# LAUNCHXL-F28377S_2.net
KiCad netlist of a schematic drawn in Altium Designer
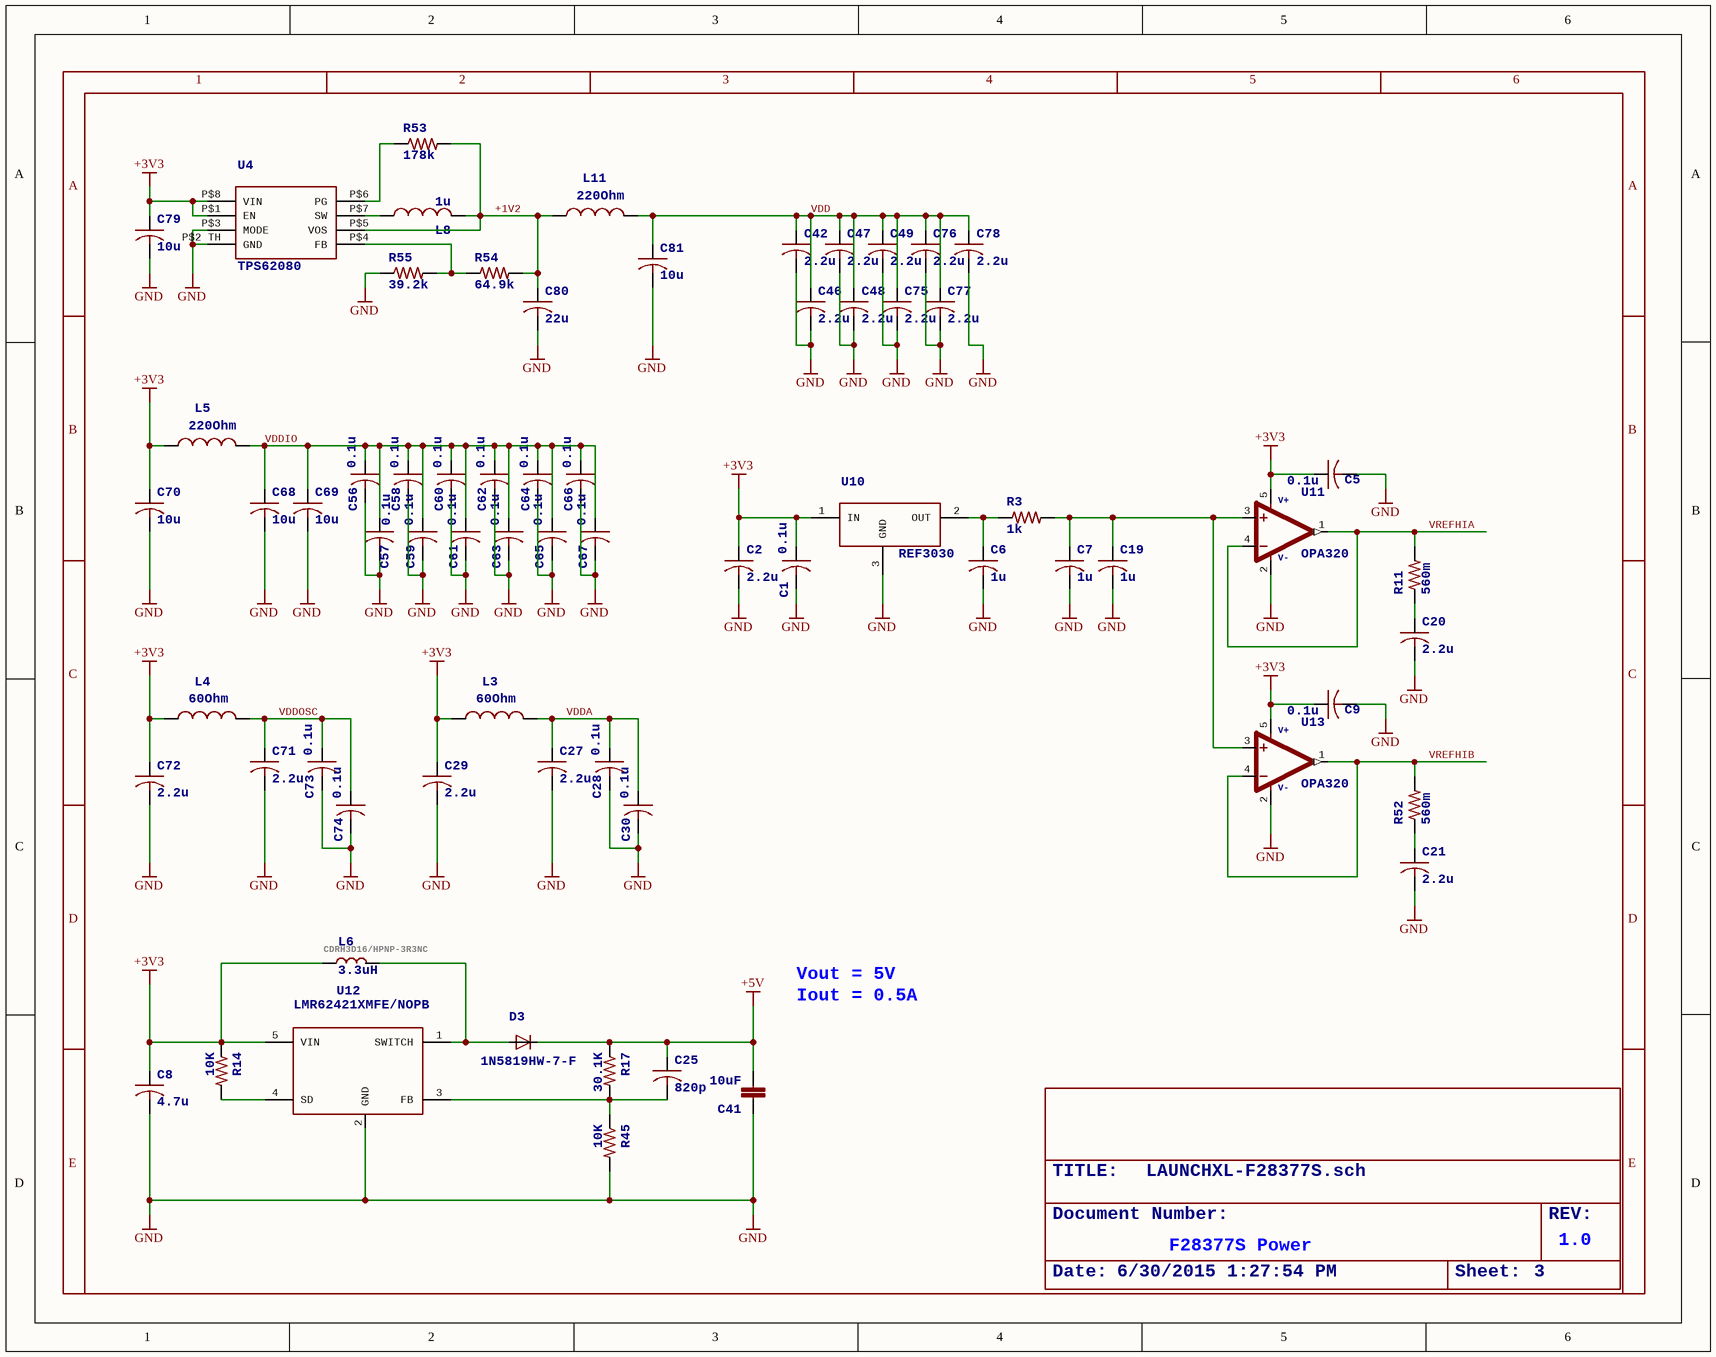
[diagram p0: LAUNCHXL-F28377S_2.SchDoc]

(export (version "E")
  (design (tool "Eeschema 10.0.6"))
  (components
    (comp (ref "C1")
      (value "0.1u")
      (footprint "C0402")
      (description "<B>CAPACITOR</B>, American symbol")
      (libsource (lib "rcl") (part "C-USC0402"))
    )
    (comp (ref "C2")
      (value "2.2u")
      (footprint "C0402")
      (description "<B>CAPACITOR</B>, American symbol")
      (libsource (lib "rcl") (part "C-USC0402"))
    )
    (comp (ref "C5")
      (value "0.1u")
      (footprint "C0402")
      (description "<B>CAPACITOR</B>, American symbol")
      (libsource (lib "rcl") (part "C-USC0402"))
    )
    (comp (ref "C6")
      (value "1u")
      (footprint "C0402")
      (description "<B>CAPACITOR</B>, American symbol")
      (libsource (lib "rcl") (part "C-USC0402"))
    )
    (comp (ref "C7")
      (value "1u")
      (footprint "C0402")
      (description "<B>CAPACITOR</B>, American symbol")
      (libsource (lib "rcl") (part "C-USC0402"))
    )
    (comp (ref "C8")
      (value "4.7u")
      (footprint "C0402")
      (description "<B>CAPACITOR</B>, American symbol")
      (libsource (lib "rcl") (part "C-USC0402"))
    )
    (comp (ref "C9")
      (value "0.1u")
      (footprint "C0402")
      (description "<B>CAPACITOR</B>, American symbol")
      (libsource (lib "rcl") (part "C-USC0402"))
    )
    (comp (ref "C19")
      (value "1u")
      (footprint "C0402")
      (description "<B>CAPACITOR</B>, American symbol")
      (libsource (lib "rcl") (part "C-USC0402"))
    )
    (comp (ref "C20")
      (value "2.2u")
      (footprint "C0402")
      (description "<B>CAPACITOR</B>, American symbol")
      (libsource (lib "rcl") (part "C-USC0402"))
    )
    (comp (ref "C21")
      (value "2.2u")
      (footprint "C0402")
      (description "<B>CAPACITOR</B>, American symbol")
      (libsource (lib "rcl") (part "C-USC0402"))
    )
    (comp (ref "C25")
      (value "820p")
      (footprint "C0402")
      (description "<B>CAPACITOR</B>, American symbol")
      (libsource (lib "rcl") (part "C-USC0402"))
    )
    (comp (ref "C27")
      (value "2.2u")
      (footprint "C0402")
      (description "<B>CAPACITOR</B>, American symbol")
      (libsource (lib "rcl") (part "C-USC0402"))
    )
    (comp (ref "C28")
      (value "0.1u")
      (footprint "C0402")
      (description "<B>CAPACITOR</B>, American symbol")
      (libsource (lib "rcl") (part "C-USC0402"))
    )
    (comp (ref "C29")
      (value "2.2u")
      (footprint "C0402")
      (description "<B>CAPACITOR</B>, American symbol")
      (libsource (lib "rcl") (part "C-USC0402"))
    )
    (comp (ref "C30")
      (value "0.1u")
      (footprint "C0402")
      (description "<B>CAPACITOR</B>, American symbol")
      (libsource (lib "rcl") (part "C-USC0402"))
    )
    (comp (ref "C41")
      (value "10uF")
      (footprint "SPARKFUN_1210")
      (description "<b>Capacitor</b>\nStandard 0603 ceramic capacitor, and 0.1\" leaded capacitor.")
      (libsource (lib "RF430FRL152H_EVM_a") (part "SPARKFUN_CAP1210"))
    )
    (comp (ref "C42")
      (value "2.2u")
      (footprint "C0402")
      (description "<B>CAPACITOR</B>, American symbol")
      (libsource (lib "rcl") (part "C-USC0402"))
    )
    (comp (ref "C46")
      (value "2.2u")
      (footprint "C0402")
      (description "<B>CAPACITOR</B>, American symbol")
      (libsource (lib "rcl") (part "C-USC0402"))
    )
    (comp (ref "C47")
      (value "2.2u")
      (footprint "C0402")
      (description "<B>CAPACITOR</B>, American symbol")
      (libsource (lib "rcl") (part "C-USC0402"))
    )
    (comp (ref "C48")
      (value "2.2u")
      (footprint "C0402")
      (description "<B>CAPACITOR</B>, American symbol")
      (libsource (lib "rcl") (part "C-USC0402"))
    )
    (comp (ref "C49")
      (value "2.2u")
      (footprint "C0402")
      (description "<B>CAPACITOR</B>, American symbol")
      (libsource (lib "rcl") (part "C-USC0402"))
    )
    (comp (ref "C56")
      (value "0.1u")
      (footprint "C0402")
      (description "<B>CAPACITOR</B>, American symbol")
      (libsource (lib "rcl") (part "C-USC0402"))
    )
    (comp (ref "C57")
      (value "0.1u")
      (footprint "C0402")
      (description "<B>CAPACITOR</B>, American symbol")
      (libsource (lib "") (part "C-USC0402_1"))
    )
    (comp (ref "C58")
      (value "0.1u")
      (footprint "C0402")
      (description "<B>CAPACITOR</B>, American symbol")
      (libsource (lib "rcl") (part "C-USC0402"))
    )
    (comp (ref "C59")
      (value "0.1u")
      (footprint "C0402")
      (description "<B>CAPACITOR</B>, American symbol")
      (libsource (lib "rcl") (part "C-USC0402"))
    )
    (comp (ref "C60")
      (value "0.1u")
      (footprint "C0402")
      (description "<B>CAPACITOR</B>, American symbol")
      (libsource (lib "rcl") (part "C-USC0402"))
    )
    (comp (ref "C61")
      (value "0.1u")
      (footprint "C0402")
      (description "<B>CAPACITOR</B>, American symbol")
      (libsource (lib "rcl") (part "C-USC0402"))
    )
    (comp (ref "C62")
      (value "0.1u")
      (footprint "C0402")
      (description "<B>CAPACITOR</B>, American symbol")
      (libsource (lib "rcl") (part "C-USC0402"))
    )
    (comp (ref "C63")
      (value "0.1u")
      (footprint "C0402")
      (description "<B>CAPACITOR</B>, American symbol")
      (libsource (lib "rcl") (part "C-USC0402"))
    )
    (comp (ref "C64")
      (value "0.1u")
      (footprint "C0402")
      (description "<B>CAPACITOR</B>, American symbol")
      (libsource (lib "rcl") (part "C-USC0402"))
    )
    (comp (ref "C65")
      (value "0.1u")
      (footprint "C0402")
      (description "<B>CAPACITOR</B>, American symbol")
      (libsource (lib "rcl") (part "C-USC0402"))
    )
    (comp (ref "C66")
      (value "0.1u")
      (footprint "C0402")
      (description "<B>CAPACITOR</B>, American symbol")
      (libsource (lib "rcl") (part "C-USC0402"))
    )
    (comp (ref "C67")
      (value "0.1u")
      (footprint "C0402")
      (description "<B>CAPACITOR</B>, American symbol")
      (libsource (lib "rcl") (part "C-USC0402"))
    )
    (comp (ref "C68")
      (value "10u")
      (footprint "C0603")
      (description "<B>CAPACITOR</B>, American symbol")
      (libsource (lib "rcl") (part "C-USC0603"))
    )
    (comp (ref "C69")
      (value "10u")
      (footprint "C0603")
      (description "<B>CAPACITOR</B>, American symbol")
      (libsource (lib "rcl") (part "C-USC0603"))
    )
    (comp (ref "C70")
      (value "10u")
      (footprint "C0603")
      (description "<B>CAPACITOR</B>, American symbol")
      (libsource (lib "rcl") (part "C-USC0603"))
    )
    (comp (ref "C71")
      (value "2.2u")
      (footprint "C0402")
      (description "<B>CAPACITOR</B>, American symbol")
      (libsource (lib "rcl") (part "C-USC0402"))
    )
    (comp (ref "C72")
      (value "2.2u")
      (footprint "C0402")
      (description "<B>CAPACITOR</B>, American symbol")
      (libsource (lib "rcl") (part "C-USC0402"))
    )
    (comp (ref "C73")
      (value "0.1u")
      (footprint "C0402")
      (description "<B>CAPACITOR</B>, American symbol")
      (libsource (lib "rcl") (part "C-USC0402"))
    )
    (comp (ref "C74")
      (value "0.1u")
      (footprint "C0402")
      (description "<B>CAPACITOR</B>, American symbol")
      (libsource (lib "rcl") (part "C-USC0402"))
    )
    (comp (ref "C75")
      (value "2.2u")
      (footprint "C0402")
      (description "<B>CAPACITOR</B>, American symbol")
      (libsource (lib "rcl") (part "C-USC0402"))
    )
    (comp (ref "C76")
      (value "2.2u")
      (footprint "C0402")
      (description "<B>CAPACITOR</B>, American symbol")
      (libsource (lib "rcl") (part "C-USC0402"))
    )
    (comp (ref "C77")
      (value "2.2u")
      (footprint "C0402")
      (description "<B>CAPACITOR</B>, American symbol")
      (libsource (lib "rcl") (part "C-USC0402"))
    )
    (comp (ref "C78")
      (value "2.2u")
      (footprint "C0402")
      (description "<B>CAPACITOR</B>, American symbol")
      (libsource (lib "rcl") (part "C-USC0402"))
    )
    (comp (ref "C79")
      (value "10u")
      (footprint "C0603")
      (description "<B>CAPACITOR</B>, American symbol")
      (libsource (lib "rcl") (part "C-USC0603"))
    )
    (comp (ref "C80")
      (value "22u")
      (footprint "C0603")
      (description "<B>CAPACITOR</B>, American symbol")
      (libsource (lib "rcl") (part "C-USC0603"))
    )
    (comp (ref "C81")
      (value "10u")
      (footprint "C0603")
      (description "<B>CAPACITOR</B>, American symbol")
      (libsource (lib "rcl") (part "C-USC0603"))
    )
    (comp (ref "D3")
      (value "1N5819HW-7-F")
      (footprint "SOD123")
      (description "<B>DIODE</B><p>\nhigh speed (Philips)")
      (libsource (lib "diode") (part "1N4148"))
    )
    (comp (ref "FRAME8")
      (value "FRAME_A_L")
      (description "<b>FRAME</b> A Size , 8 1/2 x 11 INCH, Landscape<p>")
      (fields
        (field (name "DATE:") "Date:")
        (field (name ">LAST_DATE_TIME") "6/30/2015 1:27:54 PM")
        (field (name "SHEET:") "Sheet:")
        (field (name ">SHEET") "3")
        (field (name "REV:") "REV:")
        (field (name "TITLE:") "TITLE:")
        (field (name "DOCUMENT NUMBER:") "Document Number:")
        (field (name ">DRAWING_NAME") "LAUNCHXL-F28377S.sch")
      )
      (libsource (lib "frames") (part "FRAME_A_L"))
    )
    (comp (ref "L3")
      (value "60Ohm")
      (footprint "R0402")
      (description "<B>INDUCTOR</B>, American symbol")
      (libsource (lib "rcl") (part "L-US0402"))
    )
    (comp (ref "L4")
      (value "60Ohm")
      (footprint "R0402")
      (description "<B>INDUCTOR</B>, American symbol")
      (libsource (lib "rcl") (part "L-US0402"))
    )
    (comp (ref "L5")
      (value "220Ohm")
      (footprint "R0402")
      (description "<B>INDUCTOR</B>, American symbol")
      (libsource (lib "rcl") (part "L-US0402"))
    )
    (comp (ref "L6")
      (value "3.3uH")
      (footprint "INDUCT-3_7*3_5")
      (libsource (lib "LAUNCHXL-F28027") (part "VLF4012A"))
    )
    (comp (ref "L8")
      (value "1u")
      (footprint "L1212")
      (description "<B>INDUCTOR</B>, American symbol")
      (libsource (lib "LAUNCHXL-F28377S") (part "L-USL1212"))
    )
    (comp (ref "L11")
      (value "220Ohm")
      (footprint "R0402")
      (description "<B>INDUCTOR</B>, American symbol")
      (libsource (lib "rcl") (part "L-US0402"))
    )
    (comp (ref "R3")
      (value "1k")
      (footprint "R0402")
      (description "<B>RESISTOR</B>, American symbol")
      (libsource (lib "rcl") (part "R-US_R0402"))
    )
    (comp (ref "R11")
      (value "560m")
      (footprint "R0402")
      (description "<B>RESISTOR</B>, American symbol")
      (libsource (lib "rcl") (part "R-US_R0402"))
    )
    (comp (ref "R14")
      (value "10K")
      (footprint "R0402")
      (description "<B>RESISTOR</B>, American symbol")
      (libsource (lib "rcl") (part "R-US_R0402"))
    )
    (comp (ref "R17")
      (value "30.1K")
      (footprint "R0402")
      (description "<B>RESISTOR</B>, American symbol")
      (libsource (lib "rcl") (part "R-US_R0402"))
    )
    (comp (ref "R45")
      (value "10K")
      (footprint "R0402")
      (description "<B>RESISTOR</B>, American symbol")
      (libsource (lib "rcl") (part "R-US_R0402"))
    )
    (comp (ref "R52")
      (value "560m")
      (footprint "R0402")
      (description "<B>RESISTOR</B>, American symbol")
      (libsource (lib "rcl") (part "R-US_R0402"))
    )
    (comp (ref "R53")
      (value "178k")
      (footprint "R0402")
      (description "<B>RESISTOR</B>, American symbol")
      (libsource (lib "rcl") (part "R-US_R0402"))
    )
    (comp (ref "R54")
      (value "64.9k")
      (footprint "R0402")
      (description "<B>RESISTOR</B>, American symbol")
      (libsource (lib "rcl") (part "R-US_R0402"))
    )
    (comp (ref "R55")
      (value "39.2k")
      (footprint "R0402")
      (description "<B>RESISTOR</B>, American symbol")
      (libsource (lib "rcl") (part "R-US_R0402"))
    )
    (comp (ref "U4")
      (value "TPS62080")
      (footprint "SON8")
      (libsource (lib "LAUNCHXL-F28377S") (part "TPS62080"))
    )
    (comp (ref "U10")
      (value "REF3030")
      (footprint "DBZ_R-PDSO-G3")
      (libsource (lib "LAUNCHXL-F28377S") (part "REF30XX"))
    )
    (comp (ref "U11")
      (value "OPA320")
      (footprint "SOT23-5-DBV")
      (fields (field (name "V+") "V+") (field (name "V-") "V-"))
      (libsource (lib "LAUNCHXL-F28377S") (part "OPA320"))
    )
    (comp (ref "U12")
      (value "LMR62421XMFE/NOPB")
      (footprint "SOT23-5-DBV")
      (libsource (lib "LAUNCHXL-F28027") (part "LMR62421XMFE/NOPB"))
    )
    (comp (ref "U13")
      (value "OPA320")
      (footprint "SOT23-5-DBV")
      (fields (field (name "V+") "V+") (field (name "V-") "V-"))
      (libsource (lib "LAUNCHXL-F28377S") (part "OPA320"))
    )
  )
  (nets
    (net (code "1") (name "+3V3") (class "Default")
      (node (ref "C1") (pin "1") (pinfunction "1_1") (pintype "passive"))
      (node (ref "C2") (pin "1") (pinfunction "1_1") (pintype "passive"))
      (node (ref "C29") (pin "1") (pinfunction "1_1") (pintype "passive"))
      (node (ref "C5") (pin "1") (pinfunction "1_1") (pintype "passive"))
      (node (ref "C70") (pin "1") (pinfunction "1_1") (pintype "passive"))
      (node (ref "C72") (pin "1") (pinfunction "1_1") (pintype "passive"))
      (node (ref "C79") (pin "1") (pinfunction "1_1") (pintype "passive"))
      (node (ref "C8") (pin "1") (pinfunction "1_1") (pintype "passive"))
      (node (ref "C9") (pin "1") (pinfunction "1_1") (pintype "passive"))
      (node (ref "L3") (pin "1") (pinfunction "1_1") (pintype "passive"))
      (node (ref "L4") (pin "1") (pinfunction "1_1") (pintype "passive"))
      (node (ref "L5") (pin "1") (pinfunction "1_1") (pintype "passive"))
      (node (ref "L6") (pin "P$1") (pinfunction "1_P$1") (pintype "passive"))
      (node (ref "R14") (pin "1") (pinfunction "1_1") (pintype "passive"))
      (node (ref "U10") (pin "1") (pinfunction "IN_1") (pintype "passive"))
      (node (ref "U11") (pin "5") (pinfunction "V+_5") (pintype "power_in"))
      (node (ref "U12") (pin "5") (pinfunction "VIN_5") (pintype "passive"))
      (node (ref "U13") (pin "5") (pinfunction "V+_5") (pintype "power_in"))
      (node (ref "U4") (pin "P$1") (pinfunction "EN_P$1") (pintype "passive"))
      (node (ref "U4") (pin "P$8") (pinfunction "VIN_P$8") (pintype "passive"))
    )
    (net (code "2") (name "+5V") (class "Default")
      (node (ref "C25") (pin "1") (pinfunction "1_1") (pintype "passive"))
      (node (ref "C41") (pin "2") (pinfunction "2_2") (pintype "passive"))
      (node (ref "D3") (pin "C") (pinfunction "C_C") (pintype "passive"))
      (node (ref "R17") (pin "1") (pinfunction "1_1") (pintype "passive"))
    )
    (net (code "3") (name "/+1V2") (class "Default")
      (node (ref "C80") (pin "1") (pinfunction "1_1") (pintype "passive"))
      (node (ref "L11") (pin "1") (pinfunction "1_1") (pintype "passive"))
      (node (ref "L8") (pin "P$2") (pinfunction "2_P$2") (pintype "passive"))
      (node (ref "R53") (pin "2") (pinfunction "2_2") (pintype "passive"))
      (node (ref "R54") (pin "2") (pinfunction "2_2") (pintype "passive"))
      (node (ref "U4") (pin "P$5") (pinfunction "VOS_P$5") (pintype "passive"))
    )
    (net (code "4") (name "/VDD") (class "Default")
      (node (ref "C42") (pin "1") (pinfunction "1_1") (pintype "passive"))
      (node (ref "C46") (pin "1") (pinfunction "1_1") (pintype "passive"))
      (node (ref "C47") (pin "1") (pinfunction "1_1") (pintype "passive"))
      (node (ref "C48") (pin "1") (pinfunction "1_1") (pintype "passive"))
      (node (ref "C49") (pin "1") (pinfunction "1_1") (pintype "passive"))
      (node (ref "C75") (pin "1") (pinfunction "1_1") (pintype "passive"))
      (node (ref "C76") (pin "1") (pinfunction "1_1") (pintype "passive"))
      (node (ref "C77") (pin "1") (pinfunction "1_1") (pintype "passive"))
      (node (ref "C78") (pin "1") (pinfunction "1_1") (pintype "passive"))
      (node (ref "C81") (pin "1") (pinfunction "1_1") (pintype "passive"))
      (node (ref "L11") (pin "2") (pinfunction "2_2") (pintype "passive"))
    )
    (net (code "5") (name "/VDDA") (class "Default")
      (node (ref "C27") (pin "1") (pinfunction "1_1") (pintype "passive"))
      (node (ref "C28") (pin "1") (pinfunction "1_1") (pintype "passive"))
      (node (ref "C30") (pin "1") (pinfunction "1_1") (pintype "passive"))
      (node (ref "L3") (pin "2") (pinfunction "2_2") (pintype "passive"))
    )
    (net (code "6") (name "/VDDIO") (class "Default")
      (node (ref "C56") (pin "1") (pinfunction "1_1") (pintype "passive"))
      (node (ref "C57") (pin "1") (pinfunction "1_1") (pintype "passive"))
      (node (ref "C58") (pin "1") (pinfunction "1_1") (pintype "passive"))
      (node (ref "C59") (pin "1") (pinfunction "1_1") (pintype "passive"))
      (node (ref "C60") (pin "1") (pinfunction "1_1") (pintype "passive"))
      (node (ref "C61") (pin "1") (pinfunction "1_1") (pintype "passive"))
      (node (ref "C62") (pin "1") (pinfunction "1_1") (pintype "passive"))
      (node (ref "C63") (pin "1") (pinfunction "1_1") (pintype "passive"))
      (node (ref "C64") (pin "1") (pinfunction "1_1") (pintype "passive"))
      (node (ref "C65") (pin "1") (pinfunction "1_1") (pintype "passive"))
      (node (ref "C66") (pin "1") (pinfunction "1_1") (pintype "passive"))
      (node (ref "C67") (pin "1") (pinfunction "1_1") (pintype "passive"))
      (node (ref "C68") (pin "1") (pinfunction "1_1") (pintype "passive"))
      (node (ref "C69") (pin "1") (pinfunction "1_1") (pintype "passive"))
      (node (ref "L5") (pin "2") (pinfunction "2_2") (pintype "passive"))
    )
    (net (code "7") (name "/VDDOSC") (class "Default")
      (node (ref "C71") (pin "1") (pinfunction "1_1") (pintype "passive"))
      (node (ref "C73") (pin "1") (pinfunction "1_1") (pintype "passive"))
      (node (ref "C74") (pin "1") (pinfunction "1_1") (pintype "passive"))
      (node (ref "L4") (pin "2") (pinfunction "2_2") (pintype "passive"))
    )
    (net (code "8") (name "/VREFHIA") (class "Default")
      (node (ref "R11") (pin "2") (pinfunction "2_2") (pintype "passive"))
      (node (ref "U11") (pin "1") (pinfunction "OUT_1") (pintype "output"))
      (node (ref "U11") (pin "4") (pinfunction "-IN_4") (pintype "passive"))
    )
    (net (code "9") (name "/VREFHIB") (class "Default")
      (node (ref "R52") (pin "2") (pinfunction "2_2") (pintype "passive"))
      (node (ref "U13") (pin "1") (pinfunction "OUT_1") (pintype "output"))
      (node (ref "U13") (pin "4") (pinfunction "-IN_4") (pintype "passive"))
    )
    (net (code "10") (name "GND") (class "Default")
      (node (ref "C1") (pin "2") (pinfunction "2_2") (pintype "passive"))
      (node (ref "C19") (pin "2") (pinfunction "2_2") (pintype "passive"))
      (node (ref "C2") (pin "2") (pinfunction "2_2") (pintype "passive"))
      (node (ref "C20") (pin "2") (pinfunction "2_2") (pintype "passive"))
      (node (ref "C21") (pin "2") (pinfunction "2_2") (pintype "passive"))
      (node (ref "C27") (pin "2") (pinfunction "2_2") (pintype "passive"))
      (node (ref "C28") (pin "2") (pinfunction "2_2") (pintype "passive"))
      (node (ref "C29") (pin "2") (pinfunction "2_2") (pintype "passive"))
      (node (ref "C30") (pin "2") (pinfunction "2_2") (pintype "passive"))
      (node (ref "C41") (pin "1") (pinfunction "1_1") (pintype "passive"))
      (node (ref "C42") (pin "2") (pinfunction "2_2") (pintype "passive"))
      (node (ref "C46") (pin "2") (pinfunction "2_2") (pintype "passive"))
      (node (ref "C47") (pin "2") (pinfunction "2_2") (pintype "passive"))
      (node (ref "C48") (pin "2") (pinfunction "2_2") (pintype "passive"))
      (node (ref "C49") (pin "2") (pinfunction "2_2") (pintype "passive"))
      (node (ref "C5") (pin "2") (pinfunction "2_2") (pintype "passive"))
      (node (ref "C56") (pin "2") (pinfunction "2_2") (pintype "passive"))
      (node (ref "C57") (pin "2") (pinfunction "2_2") (pintype "passive"))
      (node (ref "C58") (pin "2") (pinfunction "2_2") (pintype "passive"))
      (node (ref "C59") (pin "2") (pinfunction "2_2") (pintype "passive"))
      (node (ref "C6") (pin "2") (pinfunction "2_2") (pintype "passive"))
      (node (ref "C60") (pin "2") (pinfunction "2_2") (pintype "passive"))
      (node (ref "C61") (pin "2") (pinfunction "2_2") (pintype "passive"))
      (node (ref "C62") (pin "2") (pinfunction "2_2") (pintype "passive"))
      (node (ref "C63") (pin "2") (pinfunction "2_2") (pintype "passive"))
      (node (ref "C64") (pin "2") (pinfunction "2_2") (pintype "passive"))
      (node (ref "C65") (pin "2") (pinfunction "2_2") (pintype "passive"))
      (node (ref "C66") (pin "2") (pinfunction "2_2") (pintype "passive"))
      (node (ref "C67") (pin "2") (pinfunction "2_2") (pintype "passive"))
      (node (ref "C68") (pin "2") (pinfunction "2_2") (pintype "passive"))
      (node (ref "C69") (pin "2") (pinfunction "2_2") (pintype "passive"))
      (node (ref "C7") (pin "2") (pinfunction "2_2") (pintype "passive"))
      (node (ref "C70") (pin "2") (pinfunction "2_2") (pintype "passive"))
      (node (ref "C71") (pin "2") (pinfunction "2_2") (pintype "passive"))
      (node (ref "C72") (pin "2") (pinfunction "2_2") (pintype "passive"))
      (node (ref "C73") (pin "2") (pinfunction "2_2") (pintype "passive"))
      (node (ref "C74") (pin "2") (pinfunction "2_2") (pintype "passive"))
      (node (ref "C75") (pin "2") (pinfunction "2_2") (pintype "passive"))
      (node (ref "C76") (pin "2") (pinfunction "2_2") (pintype "passive"))
      (node (ref "C77") (pin "2") (pinfunction "2_2") (pintype "passive"))
      (node (ref "C78") (pin "2") (pinfunction "2_2") (pintype "passive"))
      (node (ref "C79") (pin "2") (pinfunction "2_2") (pintype "passive"))
      (node (ref "C8") (pin "2") (pinfunction "2_2") (pintype "passive"))
      (node (ref "C80") (pin "2") (pinfunction "2_2") (pintype "passive"))
      (node (ref "C81") (pin "2") (pinfunction "2_2") (pintype "passive"))
      (node (ref "C9") (pin "2") (pinfunction "2_2") (pintype "passive"))
      (node (ref "R45") (pin "2") (pinfunction "2_2") (pintype "passive"))
      (node (ref "R55") (pin "1") (pinfunction "1_1") (pintype "passive"))
      (node (ref "U10") (pin "3") (pinfunction "GND_3") (pintype "passive"))
      (node (ref "U11") (pin "2") (pinfunction "V-_2") (pintype "power_in"))
      (node (ref "U12") (pin "2") (pinfunction "GND_2") (pintype "passive"))
      (node (ref "U13") (pin "2") (pinfunction "V-_2") (pintype "power_in"))
      (node (ref "U4") (pin "P$2_TH") (pinfunction "GND_P$2_TH") (pintype "passive"))
      (node (ref "U4") (pin "P$3") (pinfunction "MODE_P$3") (pintype "passive"))
    )
    (net (code "11") (name "Net-(C20-Pad1)") (class "Default")
      (node (ref "C20") (pin "1") (pinfunction "1_1") (pintype "passive"))
      (node (ref "R11") (pin "1") (pinfunction "1_1") (pintype "passive"))
    )
    (net (code "12") (name "Net-(C21-Pad1)") (class "Default")
      (node (ref "C21") (pin "1") (pinfunction "1_1") (pintype "passive"))
      (node (ref "R52") (pin "1") (pinfunction "1_1") (pintype "passive"))
    )
    (net (code "13") (name "Net-(L6-2)") (class "Default")
      (node (ref "D3") (pin "A") (pinfunction "A_A") (pintype "passive"))
      (node (ref "L6") (pin "P$2") (pinfunction "2_P$2") (pintype "passive"))
      (node (ref "U12") (pin "1") (pinfunction "SWITCH_1") (pintype "passive"))
    )
    (net (code "14") (name "Net-(L8-1)") (class "Default")
      (node (ref "L8") (pin "P$1") (pinfunction "1_P$1") (pintype "passive"))
      (node (ref "U4") (pin "P$7") (pinfunction "SW_P$7") (pintype "passive"))
    )
    (net (code "15") (name "Net-(U4-FB)") (class "Default")
      (node (ref "R54") (pin "1") (pinfunction "1_1") (pintype "passive"))
      (node (ref "R55") (pin "2") (pinfunction "2_2") (pintype "passive"))
      (node (ref "U4") (pin "P$4") (pinfunction "FB_P$4") (pintype "passive"))
    )
    (net (code "16") (name "Net-(U4-PG)") (class "Default")
      (node (ref "R53") (pin "1") (pinfunction "1_1") (pintype "passive"))
      (node (ref "U4") (pin "P$6") (pinfunction "PG_P$6") (pintype "passive"))
    )
    (net (code "17") (name "Net-(U10-OUT)") (class "Default")
      (node (ref "C6") (pin "1") (pinfunction "1_1") (pintype "passive"))
      (node (ref "R3") (pin "1") (pinfunction "1_1") (pintype "passive"))
      (node (ref "U10") (pin "2") (pinfunction "OUT_2") (pintype "passive"))
    )
    (net (code "18") (name "Net-(U11-+IN)") (class "Default")
      (node (ref "C19") (pin "1") (pinfunction "1_1") (pintype "passive"))
      (node (ref "C7") (pin "1") (pinfunction "1_1") (pintype "passive"))
      (node (ref "R3") (pin "2") (pinfunction "2_2") (pintype "passive"))
      (node (ref "U11") (pin "3") (pinfunction "+IN_3") (pintype "passive"))
      (node (ref "U13") (pin "3") (pinfunction "+IN_3") (pintype "passive"))
    )
    (net (code "19") (name "Net-(U12-FB)") (class "Default")
      (node (ref "C25") (pin "2") (pinfunction "2_2") (pintype "passive"))
      (node (ref "R17") (pin "2") (pinfunction "2_2") (pintype "passive"))
      (node (ref "R45") (pin "1") (pinfunction "1_1") (pintype "passive"))
      (node (ref "U12") (pin "3") (pinfunction "FB_3") (pintype "passive"))
    )
    (net (code "20") (name "Net-(U12-SD)") (class "Default")
      (node (ref "R14") (pin "2") (pinfunction "2_2") (pintype "passive"))
      (node (ref "U12") (pin "4") (pinfunction "SD_4") (pintype "passive"))
    )
  )
)
